# baseI2C_milling.net
KiCad netlist of a schematic drawn in EAGLE
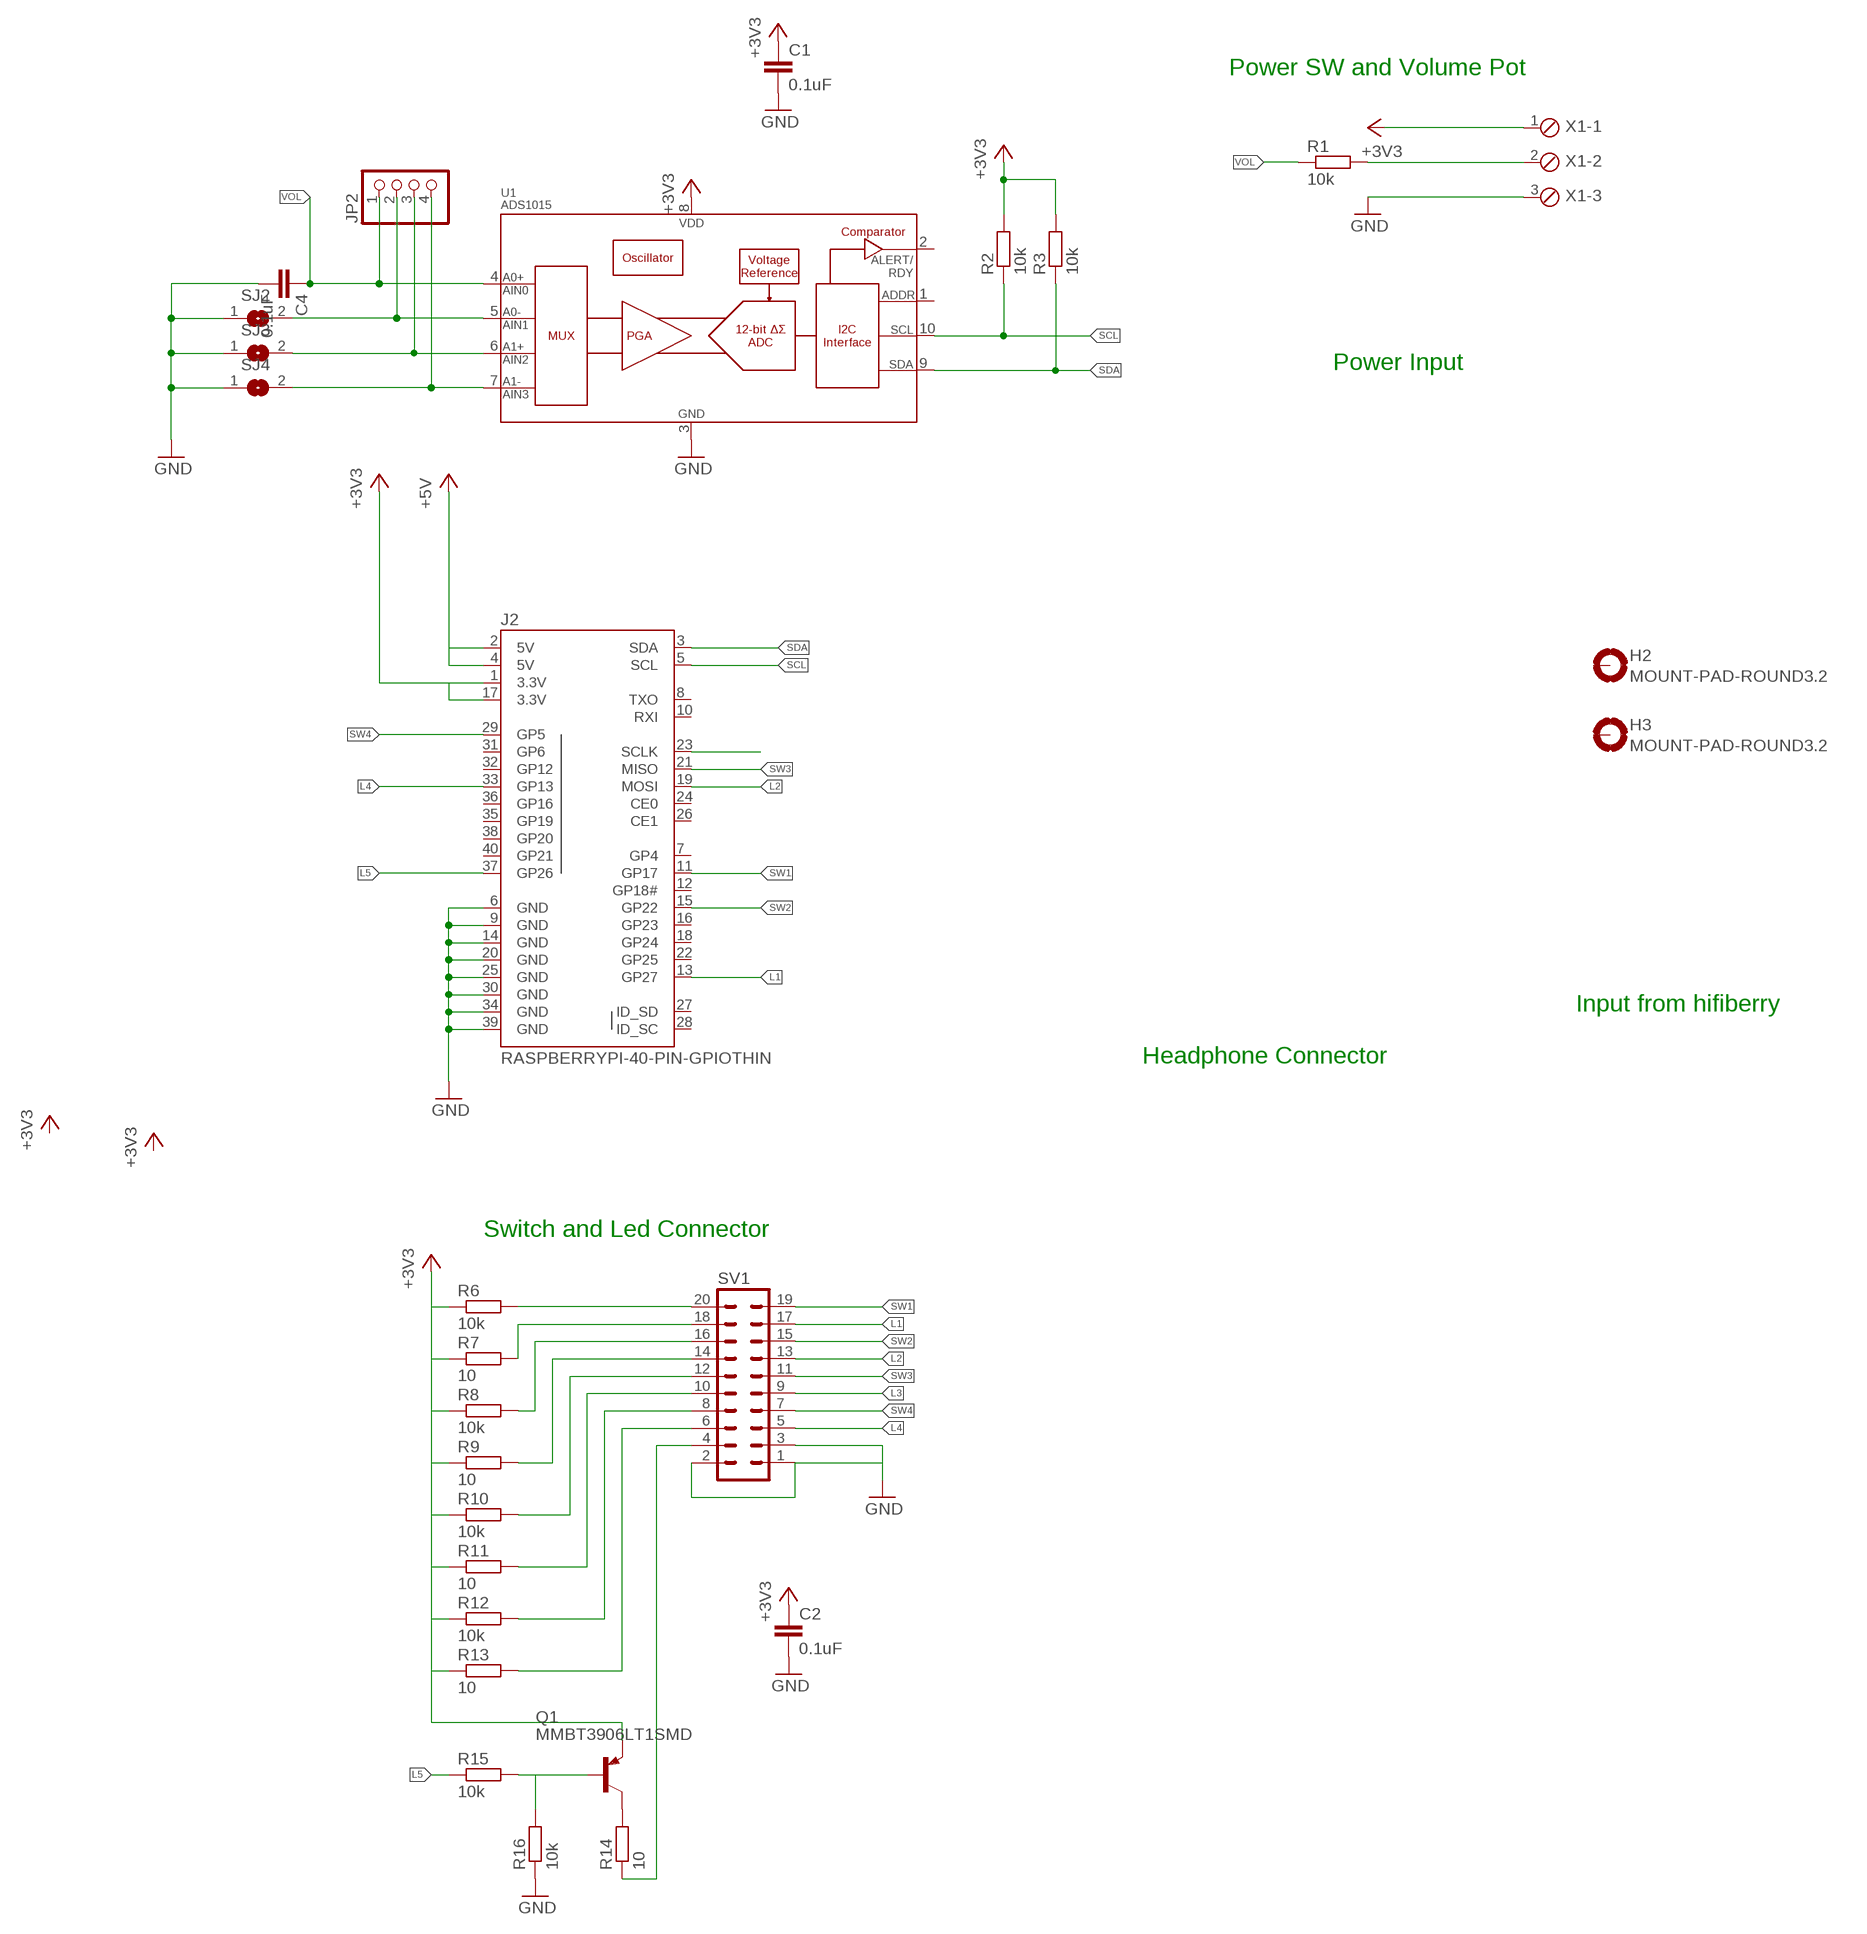
[diagram p0: schematic, sheet 1]

(export (version "E")
  (design (tool "Eeschema 10.0.6"))
  (components
    (comp (ref "C1")
      (value "0.1uF")
      (footprint "eagle-import:C0805")
      (libsource (lib "eagle-import") (part "C-EUC0805"))
    )
    (comp (ref "C2")
      (value "0.1uF")
      (footprint "eagle-import:C0805")
      (libsource (lib "eagle-import") (part "C-EUC0805"))
    )
    (comp (ref "C4")
      (value "0.1uF")
      (footprint "eagle-import:C0805")
      (libsource (lib "eagle-import") (part "C-EUC0805"))
    )
    (comp (ref "H2")
      (value "MOUNT-PAD-ROUND3.2")
      (footprint "eagle-import:3,2-PAD")
      (libsource (lib "eagle-import") (part "MOUNT-PAD-ROUND3.2"))
    )
    (comp (ref "H3")
      (value "MOUNT-PAD-ROUND3.2")
      (footprint "eagle-import:3,2-PAD")
      (libsource (lib "eagle-import") (part "MOUNT-PAD-ROUND3.2"))
    )
    (comp (ref "J2")
      (value "RASPBERRYPI-40-PIN-GPIOTHIN")
      (footprint "eagle-import:2X20-SHROUDED-THIN")
      (libsource (lib "eagle-import") (part "RASPBERRYPI-40-PIN-GPIOTHIN"))
    )
    (comp (ref "JP2")
      (value "PINHD-1X4")
      (footprint "eagle-import:1X04")
      (libsource (lib "eagle-import") (part "PINHD-1X4"))
    )
    (comp (ref "Q1")
      (value "MMBT3906LT1SMD")
      (footprint "eagle-import:SOT23-BEC")
      (libsource (lib "eagle-import") (part "MMBT3906SMDLT1"))
    )
    (comp (ref "R1")
      (value "10k")
      (footprint "eagle-import:R0805")
      (libsource (lib "eagle-import") (part "R-EU_R0805"))
    )
    (comp (ref "R2")
      (value "10k")
      (footprint "eagle-import:R0805")
      (libsource (lib "eagle-import") (part "R-EU_R0805"))
    )
    (comp (ref "R3")
      (value "10k")
      (footprint "eagle-import:R0805")
      (libsource (lib "eagle-import") (part "R-EU_R0805"))
    )
    (comp (ref "R6")
      (value "10k")
      (footprint "eagle-import:R0805")
      (libsource (lib "eagle-import") (part "R-EU_R0805"))
    )
    (comp (ref "R7")
      (value "10")
      (footprint "eagle-import:R0805")
      (libsource (lib "eagle-import") (part "R-EU_R0805"))
    )
    (comp (ref "R8")
      (value "10k")
      (footprint "eagle-import:R0805")
      (libsource (lib "eagle-import") (part "R-EU_R0805"))
    )
    (comp (ref "R9")
      (value "10")
      (footprint "eagle-import:R0805")
      (libsource (lib "eagle-import") (part "R-EU_R0805"))
    )
    (comp (ref "R10")
      (value "10k")
      (footprint "eagle-import:R0805")
      (libsource (lib "eagle-import") (part "R-EU_R0805"))
    )
    (comp (ref "R11")
      (value "10")
      (footprint "eagle-import:R0805")
      (libsource (lib "eagle-import") (part "R-EU_R0805"))
    )
    (comp (ref "R12")
      (value "10k")
      (footprint "eagle-import:R0805")
      (libsource (lib "eagle-import") (part "R-EU_R0805"))
    )
    (comp (ref "R13")
      (value "10")
      (footprint "eagle-import:R0805")
      (libsource (lib "eagle-import") (part "R-EU_R0805"))
    )
    (comp (ref "R14")
      (value "10")
      (footprint "eagle-import:R0805")
      (libsource (lib "eagle-import") (part "R-EU_R0805"))
    )
    (comp (ref "R15")
      (value "10k")
      (footprint "eagle-import:R0805")
      (libsource (lib "eagle-import") (part "R-EU_R0805"))
    )
    (comp (ref "R16")
      (value "10k")
      (footprint "eagle-import:R0805")
      (libsource (lib "eagle-import") (part "R-EU_R0805"))
    )
    (comp (ref "SJ2")
      (value "SOLDERJUMPER")
      (footprint "eagle-import:SOLDERJUMPER_ARROW_NOPASTE")
      (libsource (lib "eagle-import") (part "SOLDERJUMPER"))
    )
    (comp (ref "SJ3")
      (value "SOLDERJUMPER")
      (footprint "eagle-import:SOLDERJUMPER_ARROW_NOPASTE")
      (libsource (lib "eagle-import") (part "SOLDERJUMPER"))
    )
    (comp (ref "SJ4")
      (value "SOLDERJUMPER")
      (footprint "eagle-import:SOLDERJUMPER_ARROW_NOPASTE")
      (libsource (lib "eagle-import") (part "SOLDERJUMPER"))
    )
    (comp (ref "SV1")
      (value "ML20")
      (footprint "eagle-import:ML20")
      (libsource (lib "eagle-import") (part "ML20"))
    )
    (comp (ref "U1")
      (value "ADS1015")
      (footprint "eagle-import:MSOP10")
      (libsource (lib "eagle-import") (part "ADS1015"))
    )
    (comp (ref "X1")
      (value "MPT3")
      (footprint "eagle-import:3POL254")
      (libsource (lib "eagle-import") (part "MPT3"))
    )
  )
  (nets
    (net (code "1") (name "+3V3") (class "Default")
      (node (ref "C1") (pin "1") (pinfunction "1_1") (pintype "passive"))
      (node (ref "C2") (pin "1") (pinfunction "1_1") (pintype "passive"))
      (node (ref "J2") (pin "1") (pinfunction "3.3V_1") (pintype "power_in"))
      (node (ref "J2") (pin "17") (pinfunction "3.3V_17") (pintype "power_in"))
      (node (ref "Q1") (pin "E") (pinfunction "E_E") (pintype "passive"))
      (node (ref "R10") (pin "1") (pinfunction "1_1") (pintype "passive"))
      (node (ref "R11") (pin "1") (pinfunction "1_1") (pintype "passive"))
      (node (ref "R12") (pin "1") (pinfunction "1_1") (pintype "passive"))
      (node (ref "R13") (pin "1") (pinfunction "1_1") (pintype "passive"))
      (node (ref "R2") (pin "2") (pinfunction "2_2") (pintype "passive"))
      (node (ref "R3") (pin "2") (pinfunction "2_2") (pintype "passive"))
      (node (ref "R6") (pin "1") (pinfunction "1_1") (pintype "passive"))
      (node (ref "R7") (pin "1") (pinfunction "1_1") (pintype "passive"))
      (node (ref "R8") (pin "1") (pinfunction "1_1") (pintype "passive"))
      (node (ref "R9") (pin "1") (pinfunction "1_1") (pintype "passive"))
      (node (ref "U1") (pin "8") (pinfunction "VDD_8") (pintype "bidirectional"))
      (node (ref "X1") (pin "1") (pinfunction "1_1") (pintype "passive"))
    )
    (net (code "2") (name "+5V") (class "Default")
      (node (ref "J2") (pin "2") (pinfunction "5V_2") (pintype "power_in"))
      (node (ref "J2") (pin "4") (pinfunction "5V_4") (pintype "power_in"))
    )
    (net (code "3") (name "GND") (class "Default")
      (node (ref "C1") (pin "2") (pinfunction "2_2") (pintype "passive"))
      (node (ref "C2") (pin "2") (pinfunction "2_2") (pintype "passive"))
      (node (ref "C4") (pin "2") (pinfunction "2_2") (pintype "passive"))
      (node (ref "J2") (pin "14") (pinfunction "GND_14") (pintype "power_in"))
      (node (ref "J2") (pin "20") (pinfunction "GND_20") (pintype "power_in"))
      (node (ref "J2") (pin "25") (pinfunction "GND_25") (pintype "power_in"))
      (node (ref "J2") (pin "30") (pinfunction "GND_30") (pintype "power_in"))
      (node (ref "J2") (pin "34") (pinfunction "GND_34") (pintype "power_in"))
      (node (ref "J2") (pin "39") (pinfunction "GND_39") (pintype "power_in"))
      (node (ref "J2") (pin "6") (pinfunction "GND_6") (pintype "power_in"))
      (node (ref "J2") (pin "9") (pinfunction "GND_9") (pintype "power_in"))
      (node (ref "R16") (pin "1") (pinfunction "1_1") (pintype "passive"))
      (node (ref "SJ2") (pin "1") (pinfunction "1_1") (pintype "passive"))
      (node (ref "SJ3") (pin "1") (pinfunction "1_1") (pintype "passive"))
      (node (ref "SJ4") (pin "1") (pinfunction "1_1") (pintype "passive"))
      (node (ref "SV1") (pin "1") (pinfunction "1_1") (pintype "passive"))
      (node (ref "SV1") (pin "2") (pinfunction "2_2") (pintype "passive"))
      (node (ref "SV1") (pin "3") (pinfunction "3_3") (pintype "passive"))
      (node (ref "U1") (pin "3") (pinfunction "VSS_3") (pintype "bidirectional"))
      (node (ref "X1") (pin "3") (pinfunction "1_3") (pintype "passive"))
    )
    (net (code "4") (name "L1") (class "Default")
      (node (ref "J2") (pin "13") (pinfunction "GP27_13") (pintype "bidirectional"))
      (node (ref "SV1") (pin "17") (pinfunction "17_17") (pintype "passive"))
    )
    (net (code "5") (name "L2") (class "Default")
      (node (ref "J2") (pin "19") (pinfunction "MOSI_19") (pintype "output"))
      (node (ref "SV1") (pin "13") (pinfunction "13_13") (pintype "passive"))
    )
    (net (code "6") (name "L3") (class "Default")
      (node (ref "J2") (pin "23") (pinfunction "SCLK_23") (pintype "output"))
      (node (ref "SV1") (pin "9") (pinfunction "9_9") (pintype "passive"))
    )
    (net (code "7") (name "L4") (class "Default")
      (node (ref "J2") (pin "33") (pinfunction "GP13_33") (pintype "bidirectional"))
      (node (ref "SV1") (pin "5") (pinfunction "5_5") (pintype "passive"))
    )
    (net (code "8") (name "L5") (class "Default")
      (node (ref "J2") (pin "37") (pinfunction "GP26_37") (pintype "bidirectional"))
      (node (ref "R15") (pin "1") (pinfunction "1_1") (pintype "passive"))
    )
    (net (code "9") (name "Net-(Q1-PadB)") (class "Default")
      (node (ref "Q1") (pin "B") (pinfunction "B_B") (pintype "passive"))
      (node (ref "R15") (pin "2") (pinfunction "2_2") (pintype "passive"))
      (node (ref "R16") (pin "2") (pinfunction "2_2") (pintype "passive"))
    )
    (net (code "10") (name "Net-(Q1-PadC)") (class "Default")
      (node (ref "Q1") (pin "C") (pinfunction "C_C") (pintype "passive"))
      (node (ref "R14") (pin "2") (pinfunction "2_2") (pintype "passive"))
    )
    (net (code "11") (name "Net-(R6-Pad2)") (class "Default")
      (node (ref "R6") (pin "2") (pinfunction "2_2") (pintype "passive"))
      (node (ref "SV1") (pin "20") (pinfunction "20_20") (pintype "passive"))
    )
    (net (code "12") (name "Net-(R7-Pad2)") (class "Default")
      (node (ref "R7") (pin "2") (pinfunction "2_2") (pintype "passive"))
      (node (ref "SV1") (pin "18") (pinfunction "18_18") (pintype "passive"))
    )
    (net (code "13") (name "Net-(R8-Pad2)") (class "Default")
      (node (ref "R8") (pin "2") (pinfunction "2_2") (pintype "passive"))
      (node (ref "SV1") (pin "16") (pinfunction "16_16") (pintype "passive"))
    )
    (net (code "14") (name "Net-(R9-Pad2)") (class "Default")
      (node (ref "R9") (pin "2") (pinfunction "2_2") (pintype "passive"))
      (node (ref "SV1") (pin "14") (pinfunction "14_14") (pintype "passive"))
    )
    (net (code "15") (name "Net-(R10-Pad2)") (class "Default")
      (node (ref "R10") (pin "2") (pinfunction "2_2") (pintype "passive"))
      (node (ref "SV1") (pin "12") (pinfunction "12_12") (pintype "passive"))
    )
    (net (code "16") (name "Net-(R11-Pad2)") (class "Default")
      (node (ref "R11") (pin "2") (pinfunction "2_2") (pintype "passive"))
      (node (ref "SV1") (pin "10") (pinfunction "10_10") (pintype "passive"))
    )
    (net (code "17") (name "Net-(R12-Pad2)") (class "Default")
      (node (ref "R12") (pin "2") (pinfunction "2_2") (pintype "passive"))
      (node (ref "SV1") (pin "8") (pinfunction "8_8") (pintype "passive"))
    )
    (net (code "18") (name "Net-(R13-Pad2)") (class "Default")
      (node (ref "R13") (pin "2") (pinfunction "2_2") (pintype "passive"))
      (node (ref "SV1") (pin "6") (pinfunction "6_6") (pintype "passive"))
    )
    (net (code "19") (name "Net-(R14-Pad1)") (class "Default")
      (node (ref "R14") (pin "1") (pinfunction "1_1") (pintype "passive"))
      (node (ref "SV1") (pin "4") (pinfunction "4_4") (pintype "passive"))
    )
    (net (code "20") (name "Net-(U1-AIN1)") (class "Default")
      (node (ref "JP2") (pin "2") (pinfunction "2_2") (pintype "passive"))
      (node (ref "SJ2") (pin "2") (pinfunction "2_2") (pintype "passive"))
      (node (ref "U1") (pin "5") (pinfunction "AIN1_5") (pintype "bidirectional"))
    )
    (net (code "21") (name "Net-(U1-AIN2)") (class "Default")
      (node (ref "JP2") (pin "3") (pinfunction "3_3") (pintype "passive"))
      (node (ref "SJ3") (pin "2") (pinfunction "2_2") (pintype "passive"))
      (node (ref "U1") (pin "6") (pinfunction "AIN2_6") (pintype "bidirectional"))
    )
    (net (code "22") (name "Net-(U1-AIN3)") (class "Default")
      (node (ref "JP2") (pin "4") (pinfunction "4_4") (pintype "passive"))
      (node (ref "SJ4") (pin "2") (pinfunction "2_2") (pintype "passive"))
      (node (ref "U1") (pin "7") (pinfunction "AIN3_7") (pintype "bidirectional"))
    )
    (net (code "23") (name "Net-(X1B-1)") (class "Default")
      (node (ref "R1") (pin "2") (pinfunction "2_2") (pintype "passive"))
      (node (ref "X1") (pin "2") (pinfunction "1_2") (pintype "passive"))
    )
    (net (code "24") (name "SCL") (class "Default")
      (node (ref "J2") (pin "5") (pinfunction "SCL_5") (pintype "bidirectional"))
      (node (ref "R2") (pin "1") (pinfunction "1_1") (pintype "passive"))
      (node (ref "U1") (pin "10") (pinfunction "SCL_10") (pintype "bidirectional"))
    )
    (net (code "25") (name "SDA") (class "Default")
      (node (ref "J2") (pin "3") (pinfunction "SDA_3") (pintype "bidirectional"))
      (node (ref "R3") (pin "1") (pinfunction "1_1") (pintype "passive"))
      (node (ref "U1") (pin "9") (pinfunction "SDA_9") (pintype "bidirectional"))
    )
    (net (code "26") (name "SW1") (class "Default")
      (node (ref "J2") (pin "11") (pinfunction "GP17_11") (pintype "bidirectional"))
      (node (ref "SV1") (pin "19") (pinfunction "19_19") (pintype "passive"))
    )
    (net (code "27") (name "SW2") (class "Default")
      (node (ref "J2") (pin "15") (pinfunction "GP22_15") (pintype "bidirectional"))
      (node (ref "SV1") (pin "15") (pinfunction "15_15") (pintype "passive"))
    )
    (net (code "28") (name "SW3") (class "Default")
      (node (ref "J2") (pin "21") (pinfunction "MISO_21") (pintype "input"))
      (node (ref "SV1") (pin "11") (pinfunction "11_11") (pintype "passive"))
    )
    (net (code "29") (name "SW4") (class "Default")
      (node (ref "J2") (pin "29") (pinfunction "GP5_29") (pintype "bidirectional"))
      (node (ref "SV1") (pin "7") (pinfunction "7_7") (pintype "passive"))
    )
    (net (code "30") (name "VOL") (class "Default")
      (node (ref "C4") (pin "1") (pinfunction "1_1") (pintype "passive"))
      (node (ref "JP2") (pin "1") (pinfunction "1_1") (pintype "passive"))
      (node (ref "R1") (pin "1") (pinfunction "1_1") (pintype "passive"))
      (node (ref "U1") (pin "4") (pinfunction "AIN0_4") (pintype "bidirectional"))
    )
    (net (code "31") (name "unconnected-(H2-MOUNT-PadB3,2)") (class "Default")
      (node (ref "H2") (pin "B3,2") (pinfunction "MOUNT_B3,2") (pintype "passive"))
    )
    (net (code "32") (name "unconnected-(H3-MOUNT-PadB3,2)") (class "Default")
      (node (ref "H3") (pin "B3,2") (pinfunction "MOUNT_B3,2") (pintype "passive"))
    )
    (net (code "33") (name "unconnected-(J2-CE0-Pad24)") (class "Default")
      (node (ref "J2") (pin "24") (pinfunction "CE0_24") (pintype "output"))
    )
    (net (code "34") (name "unconnected-(J2-CE1-Pad26)") (class "Default")
      (node (ref "J2") (pin "26") (pinfunction "CE1_26") (pintype "output"))
    )
    (net (code "35") (name "unconnected-(J2-GP4-Pad7)") (class "Default")
      (node (ref "J2") (pin "7") (pinfunction "GP4_7") (pintype "bidirectional"))
    )
    (net (code "36") (name "unconnected-(J2-GP6-Pad31)") (class "Default")
      (node (ref "J2") (pin "31") (pinfunction "GP6_31") (pintype "bidirectional"))
    )
    (net (code "37") (name "unconnected-(J2-GP12-Pad32)") (class "Default")
      (node (ref "J2") (pin "32") (pinfunction "GP12_32") (pintype "bidirectional"))
    )
    (net (code "38") (name "unconnected-(J2-GP16-Pad36)") (class "Default")
      (node (ref "J2") (pin "36") (pinfunction "GP16_36") (pintype "bidirectional"))
    )
    (net (code "39") (name "unconnected-(J2-GP18#-Pad12)") (class "Default")
      (node (ref "J2") (pin "12") (pinfunction "GP18#_12") (pintype "bidirectional"))
    )
    (net (code "40") (name "unconnected-(J2-GP19-Pad35)") (class "Default")
      (node (ref "J2") (pin "35") (pinfunction "GP19_35") (pintype "bidirectional"))
    )
    (net (code "41") (name "unconnected-(J2-GP20-Pad38)") (class "Default")
      (node (ref "J2") (pin "38") (pinfunction "GP20_38") (pintype "bidirectional"))
    )
    (net (code "42") (name "unconnected-(J2-GP21-Pad40)") (class "Default")
      (node (ref "J2") (pin "40") (pinfunction "GP21_40") (pintype "bidirectional"))
    )
    (net (code "43") (name "unconnected-(J2-GP23-Pad16)") (class "Default")
      (node (ref "J2") (pin "16") (pinfunction "GP23_16") (pintype "bidirectional"))
    )
    (net (code "44") (name "unconnected-(J2-GP24-Pad18)") (class "Default")
      (node (ref "J2") (pin "18") (pinfunction "GP24_18") (pintype "bidirectional"))
    )
    (net (code "45") (name "unconnected-(J2-GP25-Pad22)") (class "Default")
      (node (ref "J2") (pin "22") (pinfunction "GP25_22") (pintype "bidirectional"))
    )
    (net (code "46") (name "unconnected-(J2-ID_SC-Pad28)") (class "Default")
      (node (ref "J2") (pin "28") (pinfunction "ID_SC_28") (pintype "bidirectional"))
    )
    (net (code "47") (name "unconnected-(J2-ID_SD-Pad27)") (class "Default")
      (node (ref "J2") (pin "27") (pinfunction "ID_SD_27") (pintype "bidirectional"))
    )
    (net (code "48") (name "unconnected-(J2-RXI-Pad10)") (class "Default")
      (node (ref "J2") (pin "10") (pinfunction "RXI_10") (pintype "input"))
    )
    (net (code "49") (name "unconnected-(J2-TXO-Pad8)") (class "Default")
      (node (ref "J2") (pin "8") (pinfunction "TXO_8") (pintype "output"))
    )
    (net (code "50") (name "unconnected-(U1-ADDR-Pad1)") (class "Default")
      (node (ref "U1") (pin "1") (pinfunction "ADDR_1") (pintype "bidirectional"))
    )
    (net (code "51") (name "unconnected-(U1-ALERT{slash}RDY-Pad2)") (class "Default")
      (node (ref "U1") (pin "2") (pinfunction "ALERT/RDY_2") (pintype "bidirectional"))
    )
  )
)
